# BD0008_1_1x.net
KiCad netlist of a schematic drawn in EAGLE
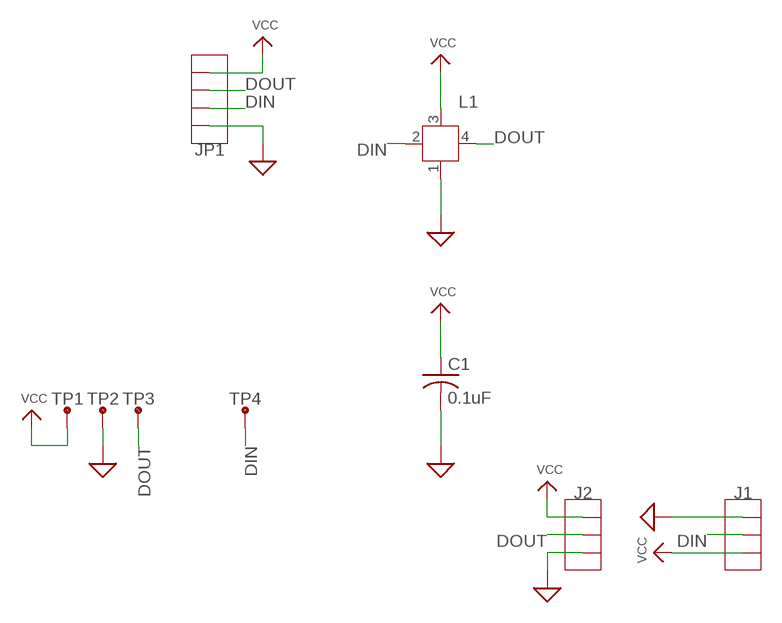
[diagram p0: schematic, sheet 1]

(export (version "E")
  (design (tool "Eeschema 10.0.6"))
  (components
    (comp (ref "C1")
      (value "0.1uF")
      (footprint "eagle-import:C0402")
      (libsource (lib "eagle-import") (part "C-USC0402"))
    )
    (comp (ref "J1")
      (value "HEADER_1X3MALE")
      (footprint "eagle-import:M3SMD")
      (libsource (lib "eagle-import") (part "HEADER_1X3MALE"))
    )
    (comp (ref "J2")
      (value "HEADER_1X3FEMALE")
      (footprint "eagle-import:F3SMD")
      (libsource (lib "eagle-import") (part "HEADER_1X3FEMALE"))
    )
    (comp (ref "JP1")
      (value "HEADER_1X4S")
      (footprint "eagle-import:1X04")
      (libsource (lib "eagle-import") (part "HEADER_1X4S"))
    )
    (comp (ref "L1")
      (value "WS2812B")
      (footprint "eagle-import:SK6812")
      (libsource (lib "eagle-import") (part "WS2812B"))
    )
    (comp (ref "TP1")
      (value "VCC")
      (footprint "eagle-import:TEST_POINT")
      (libsource (lib "eagle-import") (part "TEST_POINT"))
    )
    (comp (ref "TP2")
      (value "GND")
      (footprint "eagle-import:TEST_POINT")
      (libsource (lib "eagle-import") (part "TEST_POINT"))
    )
    (comp (ref "TP3")
      (value "DOUT")
      (footprint "eagle-import:TEST_POINT")
      (libsource (lib "eagle-import") (part "TEST_POINT"))
    )
    (comp (ref "TP4")
      (value "DIN")
      (footprint "eagle-import:TEST_POINT")
      (libsource (lib "eagle-import") (part "TEST_POINT"))
    )
  )
  (nets
    (net (code "1") (name "/DIN") (class "Default")
      (node (ref "J1") (pin "2") (pinfunction "P$2_2") (pintype "bidirectional"))
      (node (ref "JP1") (pin "2") (pinfunction "P$2_2") (pintype "bidirectional"))
      (node (ref "L1") (pin "2") (pinfunction "DIN_2") (pintype "bidirectional"))
      (node (ref "TP4") (pin "P$1") (pinfunction "P$1_P$1") (pintype "input"))
    )
    (net (code "2") (name "/DOUT") (class "Default")
      (node (ref "J2") (pin "2A") (pinfunction "P$2_2A") (pintype "bidirectional"))
      (node (ref "J2") (pin "2B") (pinfunction "P$2_2B") (pintype "bidirectional"))
      (node (ref "JP1") (pin "3") (pinfunction "P$3_3") (pintype "bidirectional"))
      (node (ref "L1") (pin "4") (pinfunction "DOUT_4") (pintype "bidirectional"))
      (node (ref "TP3") (pin "P$1") (pinfunction "P$1_P$1") (pintype "input"))
    )
    (net (code "3") (name "SUP") (class "Default")
      (node (ref "C1") (pin "2") (pinfunction "2_2") (pintype "passive"))
      (node (ref "J1") (pin "1") (pinfunction "P$1_1") (pintype "bidirectional"))
      (node (ref "J2") (pin "3A") (pinfunction "P$3_3A") (pintype "bidirectional"))
      (node (ref "J2") (pin "3B") (pinfunction "P$3_3B") (pintype "bidirectional"))
      (node (ref "JP1") (pin "1") (pinfunction "P$1_1") (pintype "bidirectional"))
      (node (ref "L1") (pin "1") (pinfunction "VSS_1") (pintype "bidirectional"))
      (node (ref "TP2") (pin "P$1") (pinfunction "P$1_P$1") (pintype "input"))
    )
    (net (code "4") (name "VCC") (class "Default")
      (node (ref "C1") (pin "1") (pinfunction "1_1") (pintype "passive"))
      (node (ref "J1") (pin "3") (pinfunction "P$3_3") (pintype "bidirectional"))
      (node (ref "J2") (pin "1A") (pinfunction "P$1_1A") (pintype "bidirectional"))
      (node (ref "J2") (pin "1B") (pinfunction "P$1_1B") (pintype "bidirectional"))
      (node (ref "JP1") (pin "4") (pinfunction "P$4_4") (pintype "bidirectional"))
      (node (ref "L1") (pin "3") (pinfunction "VDD_3") (pintype "bidirectional"))
      (node (ref "TP1") (pin "P$1") (pinfunction "P$1_P$1") (pintype "input"))
    )
  )
)
